# v1_1.net
KiCad netlist of a schematic drawn in Altium Designer
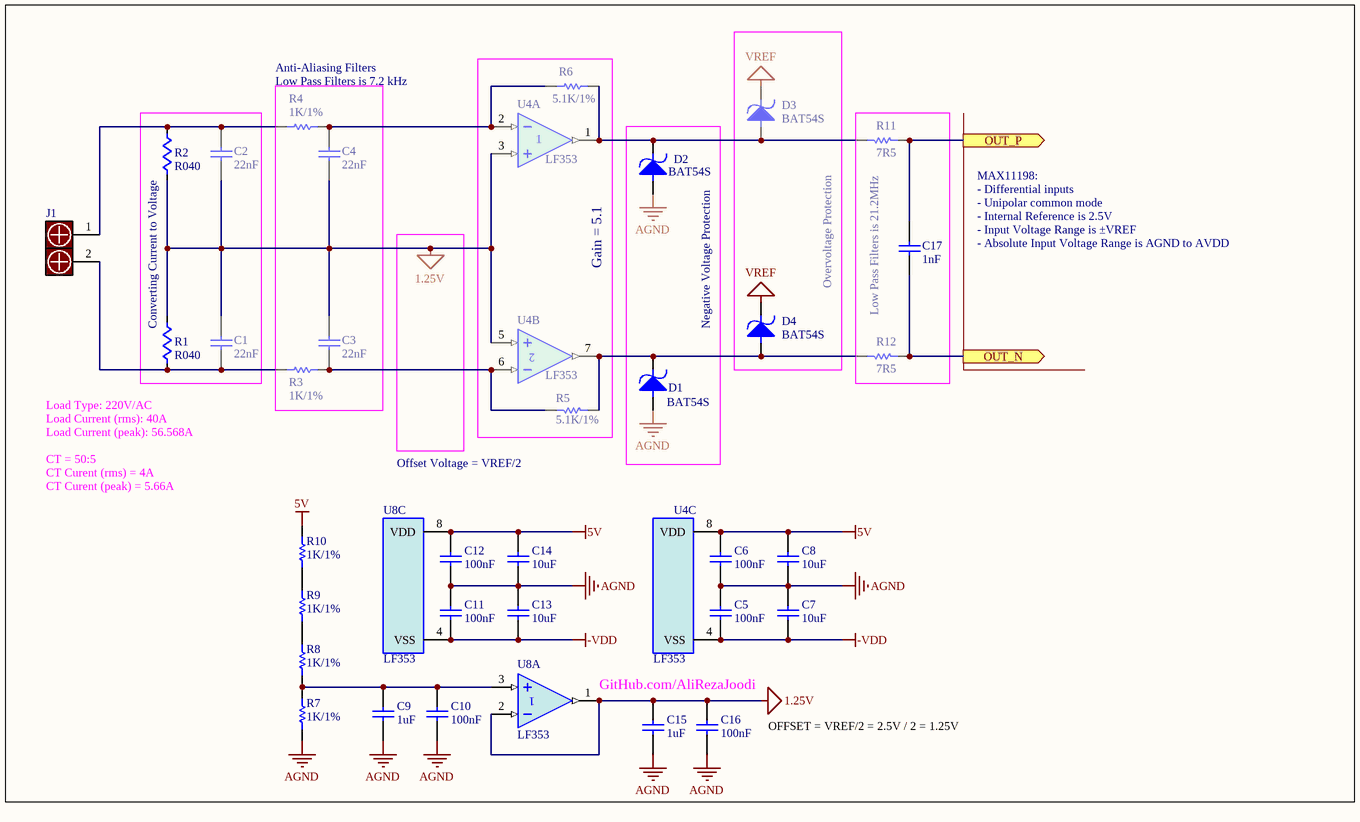
[diagram p0: v1.1.SchDoc]

(export (version "E")
  (design (tool "Eeschema 10.0.6"))
  (components
    (comp (ref "C1")
      (value "22nF")
      (footprint "Capacitor_Ceramic:SMD_0805")
      (description "Capacitor, Ceramic Multilayer, 25V, 10%")
      (libsource (lib "General") (part "Capacitor_Ceramic"))
    )
    (comp (ref "C2")
      (value "22nF")
      (footprint "Capacitor_Ceramic:SMD_0805")
      (description "Capacitor, Ceramic Multilayer, 25V, 10%")
      (libsource (lib "General") (part "Capacitor_Ceramic"))
    )
    (comp (ref "C3")
      (value "22nF")
      (footprint "Capacitor_Ceramic:SMD_0805")
      (description "Capacitor, Ceramic Multilayer, 25V, 10%")
      (libsource (lib "General") (part "Capacitor_Ceramic"))
    )
    (comp (ref "C4")
      (value "22nF")
      (footprint "Capacitor_Ceramic:SMD_0805")
      (description "Capacitor, Ceramic Multilayer, 25V, 10%")
      (libsource (lib "General") (part "Capacitor_Ceramic"))
    )
    (comp (ref "C5")
      (value "100nF")
      (footprint "Capacitor_Ceramic:SMD_0805")
      (description "Capacitor, Ceramic Multilayer, 25V, 10%")
      (libsource (lib "General") (part "Capacitor_Ceramic"))
    )
    (comp (ref "C6")
      (value "100nF")
      (footprint "Capacitor_Ceramic:SMD_0805")
      (description "Capacitor, Ceramic Multilayer, 25V, 10%")
      (libsource (lib "General") (part "Capacitor_Ceramic"))
    )
    (comp (ref "C7")
      (value "10uF")
      (footprint "Capacitor_Ceramic:SMD_0805")
      (description "Capacitor, Ceramic Multilayer, 25V, 10%")
      (libsource (lib "General") (part "Capacitor_Ceramic"))
    )
    (comp (ref "C8")
      (value "10uF")
      (footprint "Capacitor_Ceramic:SMD_0805")
      (description "Capacitor, Ceramic Multilayer, 25V, 10%")
      (libsource (lib "General") (part "Capacitor_Ceramic"))
    )
    (comp (ref "C9")
      (value "1uF")
      (footprint "Capacitor_Ceramic:SMD_0805")
      (description "Capacitor, Ceramic Multilayer, 25V, 10%")
      (libsource (lib "General") (part "Capacitor_Ceramic"))
    )
    (comp (ref "C10")
      (value "100nF")
      (footprint "Capacitor_Ceramic:SMD_0805")
      (description "Capacitor, Ceramic Multilayer, 25V, 10%")
      (libsource (lib "General") (part "Capacitor_Ceramic"))
    )
    (comp (ref "C11")
      (value "100nF")
      (footprint "Capacitor_Ceramic:SMD_0805")
      (description "Capacitor, Ceramic Multilayer, 25V, 10%")
      (libsource (lib "General") (part "Capacitor_Ceramic"))
    )
    (comp (ref "C12")
      (value "100nF")
      (footprint "Capacitor_Ceramic:SMD_0805")
      (description "Capacitor, Ceramic Multilayer, 25V, 10%")
      (libsource (lib "General") (part "Capacitor_Ceramic"))
    )
    (comp (ref "C13")
      (value "10uF")
      (footprint "Capacitor_Ceramic:SMD_0805")
      (description "Capacitor, Ceramic Multilayer, 25V, 10%")
      (libsource (lib "General") (part "Capacitor_Ceramic"))
    )
    (comp (ref "C14")
      (value "10uF")
      (footprint "Capacitor_Ceramic:SMD_0805")
      (description "Capacitor, Ceramic Multilayer, 25V, 10%")
      (libsource (lib "General") (part "Capacitor_Ceramic"))
    )
    (comp (ref "C15")
      (value "1uF")
      (footprint "Capacitor_Ceramic:SMD_0805")
      (description "Capacitor, Ceramic Multilayer, 25V, 10%")
      (libsource (lib "General") (part "Capacitor_Ceramic"))
    )
    (comp (ref "C16")
      (value "100nF")
      (footprint "Capacitor_Ceramic:SMD_0805")
      (description "Capacitor, Ceramic Multilayer, 25V, 10%")
      (libsource (lib "General") (part "Capacitor_Ceramic"))
    )
    (comp (ref "C17")
      (value "1nF")
      (footprint "Capacitor_Ceramic:SMD_0805")
      (description "Capacitor, Ceramic Multilayer, 25V, 10%")
      (libsource (lib "General") (part "Capacitor_Ceramic"))
    )
    (comp (ref "D1")
      (value "BAT54S")
      (description "Diode, Schottky")
      (libsource (lib "General") (part "Diode_Schottky"))
    )
    (comp (ref "D2")
      (value "BAT54S")
      (description "Diode, Schottky")
      (libsource (lib "General") (part "Diode_Schottky"))
    )
    (comp (ref "D3")
      (value "BAT54S")
      (description "Diode, Schottky")
      (libsource (lib "General") (part "Diode_Schottky"))
    )
    (comp (ref "D4")
      (value "BAT54S")
      (description "Diode, Schottky")
      (libsource (lib "General") (part "Diode_Schottky"))
    )
    (comp (ref "J1")
      (value "~")
      (footprint "1x2_P8.26")
      (description "Connector, Barrier Terminal Blocks, 2Pin")
      (fields (field (name "MANUFACTURER") "TE Connectivity") (field (name "PART NUMBER") "1977477-2"))
      (libsource (lib "Connector") (part "Connector1x2_Power_4Form"))
    )
    (comp (ref "R1")
      (value "R040")
      (footprint "SMD_4527")
      (description "Resistor, 2W, 1%")
      (fields (field (name "1_PART NUMBER") "WSR2R0400FEA"))
      (libsource (lib "General") (part "Resistor_2Form"))
    )
    (comp (ref "R2")
      (value "R040")
      (footprint "SMD_4527")
      (description "Resistor, 2W, 1%")
      (fields (field (name "1_PART NUMBER") "WSR2R0400FEA"))
      (libsource (lib "General") (part "Resistor_2Form"))
    )
    (comp (ref "R3")
      (value "1K/1%")
      (footprint "SMD_0805")
      (description "Resistor, 1/8W, 1%")
      (libsource (lib "General") (part "Resistor"))
    )
    (comp (ref "R4")
      (value "1K/1%")
      (footprint "SMD_0805")
      (description "Resistor, 1/8W, 1%")
      (libsource (lib "General") (part "Resistor"))
    )
    (comp (ref "R5")
      (value "5.1K/1%")
      (footprint "SMD_0805")
      (description "Resistor, 1/8W, 1%")
      (libsource (lib "General") (part "Resistor"))
    )
    (comp (ref "R6")
      (value "5.1K/1%")
      (footprint "SMD_0805")
      (description "Resistor, 1/8W, 1%")
      (libsource (lib "General") (part "Resistor"))
    )
    (comp (ref "R7")
      (value "1K/1%")
      (footprint "SMD_0805")
      (description "Resistor, 1/8W, 1%")
      (libsource (lib "General") (part "Resistor"))
    )
    (comp (ref "R8")
      (value "1K/1%")
      (footprint "SMD_0805")
      (description "Resistor, 1/8W, 1%")
      (libsource (lib "General") (part "Resistor"))
    )
    (comp (ref "R9")
      (value "1K/1%")
      (footprint "SMD_0805")
      (description "Resistor, 1/8W, 1%")
      (libsource (lib "General") (part "Resistor"))
    )
    (comp (ref "R10")
      (value "1K/1%")
      (footprint "SMD_0805")
      (description "Resistor, 1/8W, 1%")
      (libsource (lib "General") (part "Resistor"))
    )
    (comp (ref "R11")
      (value "7R5")
      (footprint "SMD_0805")
      (description "Resistor, 1/8W, 1%")
      (libsource (lib "General") (part "Resistor"))
    )
    (comp (ref "R12")
      (value "7R5")
      (footprint "SMD_0805")
      (description "Resistor, 1/8W, 1%")
      (libsource (lib "General") (part "Resistor"))
    )
    (comp (ref "U4")
      (value "LF353")
      (footprint "SOIC127P600-8CM")
      (description "IC, Op-Amp")
      (fields (field (name "MANUFACTURER") "Texas Instruments") (field (name "PART NUMBER") "LF353P"))
      (libsource (lib "IC_OpAmp") (part "Op-Amp_Form1"))
    )
    (comp (ref "U8")
      (value "LF353")
      (footprint "SOIC127P600-8CM")
      (description "IC, Op-Amp")
      (fields (field (name "MANUFACTURER") "Texas Instruments") (field (name "PART NUMBER") "LF353P"))
      (libsource (lib "IC_OpAmp") (part "Op-Amp_Form1"))
    )
  )
  (nets
    (net (code "1") (name "-VDD") (class "Default")
      (node (ref "C11") (pin "1") (pinfunction "1_1") (pintype "passive"))
      (node (ref "C13") (pin "2") (pinfunction "2_2") (pintype "passive"))
      (node (ref "C5") (pin "1") (pinfunction "1_1") (pintype "passive"))
      (node (ref "C7") (pin "2") (pinfunction "2_2") (pintype "passive"))
      (node (ref "U4") (pin "4") (pinfunction "VSS_4") (pintype "power_in"))
      (node (ref "U8") (pin "4") (pinfunction "VSS_4") (pintype "power_in"))
    )
    (net (code "2") (name "/OUT_N") (class "Default")
      (node (ref "C17") (pin "2") (pinfunction "2_2") (pintype "passive"))
      (node (ref "R12") (pin "1") (pinfunction "1_1") (pintype "passive"))
    )
    (net (code "3") (name "/OUT_P") (class "Default")
      (node (ref "C17") (pin "1") (pinfunction "1_1") (pintype "passive"))
      (node (ref "R11") (pin "1") (pinfunction "1_1") (pintype "passive"))
    )
    (net (code "4") (name "1.25V") (class "Default")
      (node (ref "C1") (pin "1") (pinfunction "1_1") (pintype "passive"))
      (node (ref "C15") (pin "1") (pinfunction "1_1") (pintype "passive"))
      (node (ref "C16") (pin "2") (pinfunction "2_2") (pintype "passive"))
      (node (ref "C2") (pin "2") (pinfunction "2_2") (pintype "passive"))
      (node (ref "C3") (pin "1") (pinfunction "1_1") (pintype "passive"))
      (node (ref "C4") (pin "2") (pinfunction "2_2") (pintype "passive"))
      (node (ref "R1") (pin "2") (pinfunction "2_2") (pintype "passive"))
      (node (ref "R2") (pin "1") (pinfunction "1_1") (pintype "passive"))
      (node (ref "U4") (pin "3") (pinfunction "IN+_3") (pintype "input"))
      (node (ref "U4") (pin "5") (pinfunction "IN+_5") (pintype "input"))
      (node (ref "U8") (pin "1") (pinfunction "OUT_1") (pintype "output"))
      (node (ref "U8") (pin "2") (pinfunction "IN-_2") (pintype "input"))
    )
    (net (code "5") (name "5V") (class "Default")
      (node (ref "C12") (pin "2") (pinfunction "2_2") (pintype "passive"))
      (node (ref "C14") (pin "1") (pinfunction "1_1") (pintype "passive"))
      (node (ref "C6") (pin "2") (pinfunction "2_2") (pintype "passive"))
      (node (ref "C8") (pin "1") (pinfunction "1_1") (pintype "passive"))
      (node (ref "R10") (pin "1") (pinfunction "1_1") (pintype "passive"))
      (node (ref "U4") (pin "8") (pinfunction "VDD_8") (pintype "passive"))
      (node (ref "U8") (pin "8") (pinfunction "VDD_8") (pintype "passive"))
    )
    (net (code "6") (name "AGND") (class "Default")
      (node (ref "C10") (pin "1") (pinfunction "1_1") (pintype "passive"))
      (node (ref "C11") (pin "2") (pinfunction "2_2") (pintype "passive"))
      (node (ref "C12") (pin "1") (pinfunction "1_1") (pintype "passive"))
      (node (ref "C13") (pin "1") (pinfunction "1_1") (pintype "passive"))
      (node (ref "C14") (pin "2") (pinfunction "2_2") (pintype "passive"))
      (node (ref "C15") (pin "2") (pinfunction "2_2") (pintype "passive"))
      (node (ref "C16") (pin "1") (pinfunction "1_1") (pintype "passive"))
      (node (ref "C5") (pin "2") (pinfunction "2_2") (pintype "passive"))
      (node (ref "C6") (pin "1") (pinfunction "1_1") (pintype "passive"))
      (node (ref "C7") (pin "1") (pinfunction "1_1") (pintype "passive"))
      (node (ref "C8") (pin "2") (pinfunction "2_2") (pintype "passive"))
      (node (ref "C9") (pin "2") (pinfunction "2_2") (pintype "passive"))
      (node (ref "D1") (pin "1") (pinfunction "A_1") (pintype "passive"))
      (node (ref "D2") (pin "1") (pinfunction "A_1") (pintype "passive"))
      (node (ref "R7") (pin "2") (pinfunction "2_2") (pintype "passive"))
    )
    (net (code "7") (name "Net-(C1-Pad2)") (class "Default")
      (node (ref "C1") (pin "2") (pinfunction "2_2") (pintype "passive"))
      (node (ref "J1") (pin "2") (pinfunction "2_2") (pintype "passive"))
      (node (ref "R1") (pin "1") (pinfunction "1_1") (pintype "passive"))
      (node (ref "R3") (pin "2") (pinfunction "2_2") (pintype "passive"))
    )
    (net (code "8") (name "Net-(C2-Pad1)") (class "Default")
      (node (ref "C2") (pin "1") (pinfunction "1_1") (pintype "passive"))
      (node (ref "J1") (pin "1") (pinfunction "1_1") (pintype "passive"))
      (node (ref "R2") (pin "2") (pinfunction "2_2") (pintype "passive"))
      (node (ref "R4") (pin "2") (pinfunction "2_2") (pintype "passive"))
    )
    (net (code "9") (name "Net-(D1-K)") (class "Default")
      (node (ref "D1") (pin "2") (pinfunction "K_2") (pintype "passive"))
      (node (ref "D4") (pin "1") (pinfunction "A_1") (pintype "passive"))
      (node (ref "R12") (pin "2") (pinfunction "2_2") (pintype "passive"))
      (node (ref "R5") (pin "1") (pinfunction "1_1") (pintype "passive"))
      (node (ref "U4") (pin "7") (pinfunction "OUT_7") (pintype "output"))
    )
    (net (code "10") (name "Net-(D2-K)") (class "Default")
      (node (ref "D2") (pin "2") (pinfunction "K_2") (pintype "passive"))
      (node (ref "D3") (pin "1") (pinfunction "A_1") (pintype "passive"))
      (node (ref "R11") (pin "2") (pinfunction "2_2") (pintype "passive"))
      (node (ref "R6") (pin "1") (pinfunction "1_1") (pintype "passive"))
      (node (ref "U4") (pin "1") (pinfunction "OUT_1") (pintype "output"))
    )
    (net (code "11") (name "Net-(R8-Pad1)") (class "Default")
      (node (ref "R8") (pin "1") (pinfunction "1_1") (pintype "passive"))
      (node (ref "R9") (pin "2") (pinfunction "2_2") (pintype "passive"))
    )
    (net (code "12") (name "Net-(R10-Pad2)") (class "Default")
      (node (ref "R10") (pin "2") (pinfunction "2_2") (pintype "passive"))
      (node (ref "R9") (pin "1") (pinfunction "1_1") (pintype "passive"))
    )
    (net (code "13") (name "Net-(U4A-IN-)") (class "Default")
      (node (ref "C4") (pin "1") (pinfunction "1_1") (pintype "passive"))
      (node (ref "R4") (pin "1") (pinfunction "1_1") (pintype "passive"))
      (node (ref "R6") (pin "2") (pinfunction "2_2") (pintype "passive"))
      (node (ref "U4") (pin "2") (pinfunction "IN-_2") (pintype "input"))
    )
    (net (code "14") (name "Net-(U4B-IN-)") (class "Default")
      (node (ref "C3") (pin "2") (pinfunction "2_2") (pintype "passive"))
      (node (ref "R3") (pin "1") (pinfunction "1_1") (pintype "passive"))
      (node (ref "R5") (pin "2") (pinfunction "2_2") (pintype "passive"))
      (node (ref "U4") (pin "6") (pinfunction "IN-_6") (pintype "input"))
    )
    (net (code "15") (name "Net-(U8A-IN+)") (class "Default")
      (node (ref "C10") (pin "2") (pinfunction "2_2") (pintype "passive"))
      (node (ref "C9") (pin "1") (pinfunction "1_1") (pintype "passive"))
      (node (ref "R7") (pin "1") (pinfunction "1_1") (pintype "passive"))
      (node (ref "R8") (pin "2") (pinfunction "2_2") (pintype "passive"))
      (node (ref "U8") (pin "3") (pinfunction "IN+_3") (pintype "input"))
    )
    (net (code "16") (name "VREF") (class "Default")
      (node (ref "D3") (pin "2") (pinfunction "K_2") (pintype "passive"))
      (node (ref "D4") (pin "2") (pinfunction "K_2") (pintype "passive"))
    )
  )
)
